# MSSRP-DAC.net
KiCad netlist of a schematic drawn in EAGLE
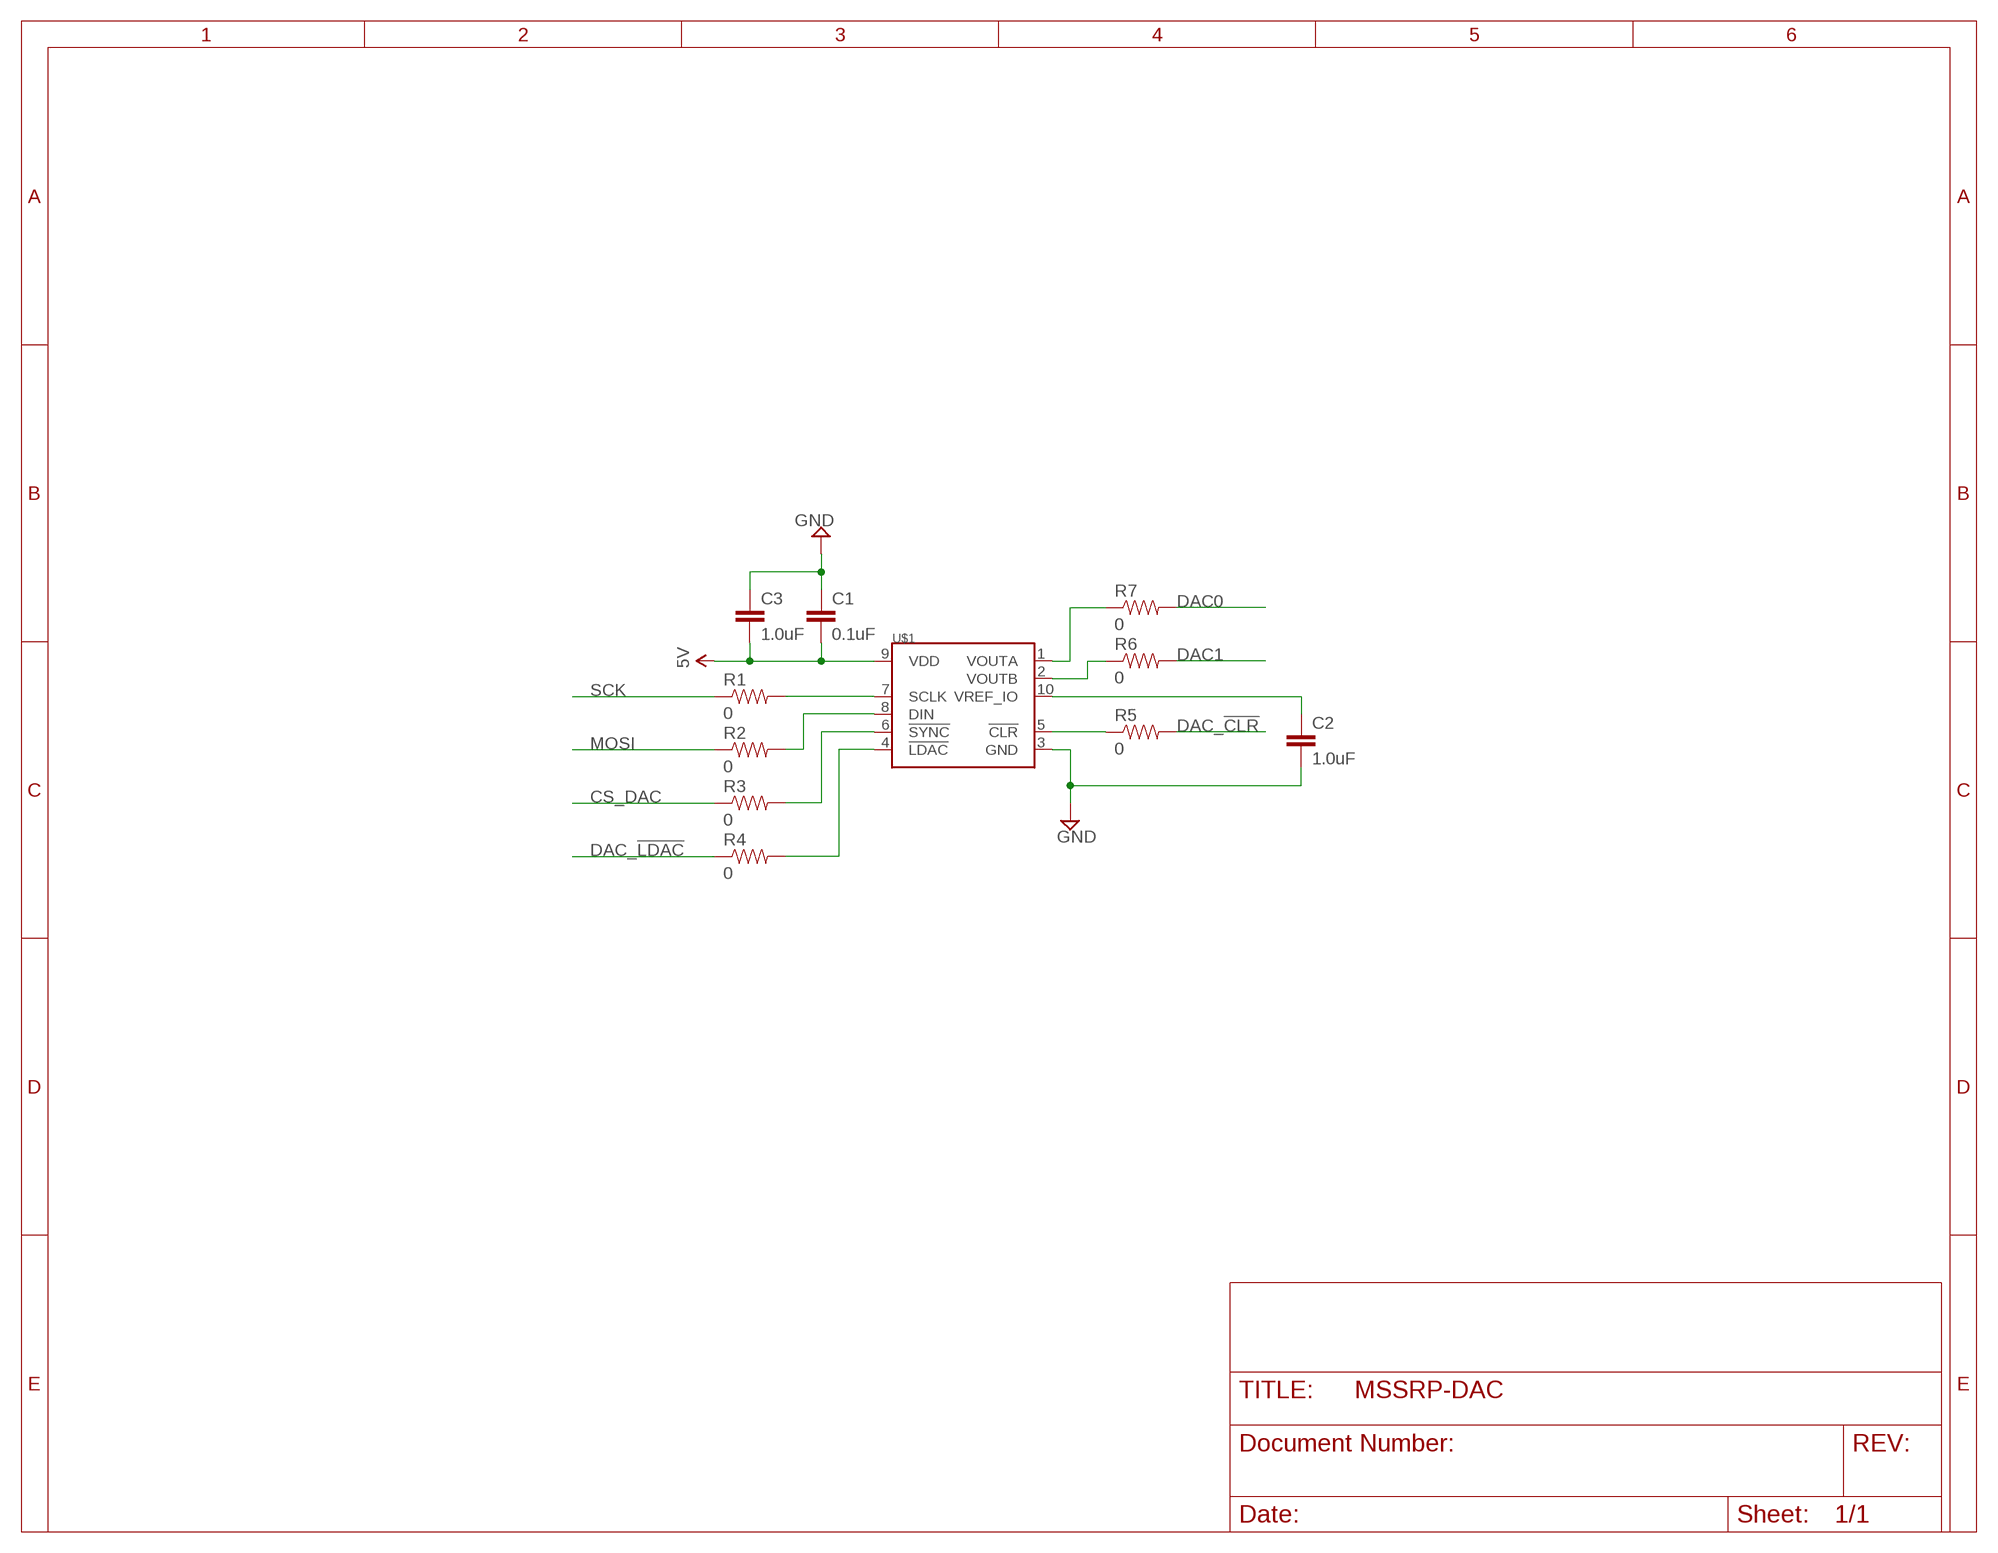
[diagram p0: schematic, sheet 1]

(export (version "E")
  (design (tool "Eeschema 10.0.6"))
  (components
    (comp (ref "C1")
      (value "0.1uF")
      (footprint "eagle-import:0603-CAP")
      (libsource (lib "eagle-import") (part "0.1UF-25V-5%(0603)"))
    )
    (comp (ref "C2")
      (value "1.0uF")
      (footprint "eagle-import:0603-CAP")
      (libsource (lib "eagle-import") (part "1.0UF-16V-10%(0603)"))
    )
    (comp (ref "C3")
      (value "1.0uF")
      (footprint "eagle-import:0603-CAP")
      (libsource (lib "eagle-import") (part "1.0UF-16V-10%(0603)"))
    )
    (comp (ref "R1")
      (value "0")
      (footprint "eagle-import:0603")
      (libsource (lib "eagle-import") (part "0OHM1/10W5%(0603)"))
    )
    (comp (ref "R2")
      (value "0")
      (footprint "eagle-import:0603")
      (libsource (lib "eagle-import") (part "0OHM1/10W5%(0603)"))
    )
    (comp (ref "R3")
      (value "0")
      (footprint "eagle-import:0603")
      (libsource (lib "eagle-import") (part "0OHM1/10W5%(0603)"))
    )
    (comp (ref "R4")
      (value "0")
      (footprint "eagle-import:0603")
      (libsource (lib "eagle-import") (part "0OHM1/10W5%(0603)"))
    )
    (comp (ref "R5")
      (value "0")
      (footprint "eagle-import:0603")
      (libsource (lib "eagle-import") (part "0OHM1/10W5%(0603)"))
    )
    (comp (ref "R6")
      (value "0")
      (footprint "eagle-import:0603")
      (libsource (lib "eagle-import") (part "0OHM1/10W5%(0603)"))
    )
    (comp (ref "R7")
      (value "0")
      (footprint "eagle-import:0603")
      (libsource (lib "eagle-import") (part "0OHM1/10W5%(0603)"))
    )
    (comp (ref "U$1")
      (value "DAC7562")
      (footprint "eagle-import:MSOP10")
      (libsource (lib "eagle-import") (part "DAC7562"))
    )
  )
  (nets
    (net (code "1") (name "/CS_DAC") (class "Default")
      (node (ref "R3") (pin "1") (pinfunction "1_1") (pintype "passive"))
    )
    (net (code "2") (name "/DAC0") (class "Default")
      (node (ref "R7") (pin "2") (pinfunction "2_2") (pintype "passive"))
    )
    (net (code "3") (name "/DAC1") (class "Default")
      (node (ref "R6") (pin "2") (pinfunction "2_2") (pintype "passive"))
    )
    (net (code "4") (name "/DAC_~{CLR}") (class "Default")
      (node (ref "R5") (pin "2") (pinfunction "2_2") (pintype "passive"))
    )
    (net (code "5") (name "/DAC_~{LDAC}") (class "Default")
      (node (ref "R4") (pin "1") (pinfunction "1_1") (pintype "passive"))
    )
    (net (code "6") (name "/MOSI") (class "Default")
      (node (ref "R2") (pin "1") (pinfunction "1_1") (pintype "passive"))
    )
    (net (code "7") (name "/SCK") (class "Default")
      (node (ref "R1") (pin "1") (pinfunction "1_1") (pintype "passive"))
    )
    (net (code "8") (name "5V") (class "Default")
      (node (ref "C1") (pin "2") (pinfunction "2_2") (pintype "passive"))
      (node (ref "C3") (pin "2") (pinfunction "2_2") (pintype "passive"))
      (node (ref "U$1") (pin "9") (pinfunction "VDD_9") (pintype "power_in"))
    )
    (net (code "9") (name "GND") (class "Default")
      (node (ref "C1") (pin "1") (pinfunction "1_1") (pintype "passive"))
      (node (ref "C2") (pin "2") (pinfunction "2_2") (pintype "passive"))
      (node (ref "C3") (pin "1") (pinfunction "1_1") (pintype "passive"))
      (node (ref "U$1") (pin "3") (pinfunction "GND_3") (pintype "power_in"))
    )
    (net (code "10") (name "Net-(U$1-DIN)") (class "Default")
      (node (ref "R2") (pin "2") (pinfunction "2_2") (pintype "passive"))
      (node (ref "U$1") (pin "8") (pinfunction "DIN_8") (pintype "input"))
    )
    (net (code "11") (name "Net-(U$1-SCLK)") (class "Default")
      (node (ref "R1") (pin "2") (pinfunction "2_2") (pintype "passive"))
      (node (ref "U$1") (pin "7") (pinfunction "SCLK_7") (pintype "bidirectional"))
    )
    (net (code "12") (name "Net-(U$1-VOUTA)") (class "Default")
      (node (ref "R7") (pin "1") (pinfunction "1_1") (pintype "passive"))
      (node (ref "U$1") (pin "1") (pinfunction "VOUTA_1") (pintype "output"))
    )
    (net (code "13") (name "Net-(U$1-VOUTB)") (class "Default")
      (node (ref "R6") (pin "1") (pinfunction "1_1") (pintype "passive"))
      (node (ref "U$1") (pin "2") (pinfunction "VOUTB_2") (pintype "output"))
    )
    (net (code "14") (name "Net-(U$1-VREF_IO)") (class "Default")
      (node (ref "C2") (pin "1") (pinfunction "1_1") (pintype "passive"))
      (node (ref "U$1") (pin "10") (pinfunction "VREF_IO_10") (pintype "bidirectional"))
    )
    (net (code "15") (name "Net-(U$1-~{CLR})") (class "Default")
      (node (ref "R5") (pin "1") (pinfunction "1_1") (pintype "passive"))
      (node (ref "U$1") (pin "5") (pinfunction "~{CLR}_5") (pintype "input"))
    )
    (net (code "16") (name "Net-(U$1-~{LDAC})") (class "Default")
      (node (ref "R4") (pin "2") (pinfunction "2_2") (pintype "passive"))
      (node (ref "U$1") (pin "4") (pinfunction "~{LDAC}_4") (pintype "input"))
    )
    (net (code "17") (name "Net-(U$1-~{SYNC})") (class "Default")
      (node (ref "R3") (pin "2") (pinfunction "2_2") (pintype "passive"))
      (node (ref "U$1") (pin "6") (pinfunction "~{SYNC}_6") (pintype "input"))
    )
  )
)
